# IR.net
KiCad netlist of a schematic drawn in EAGLE
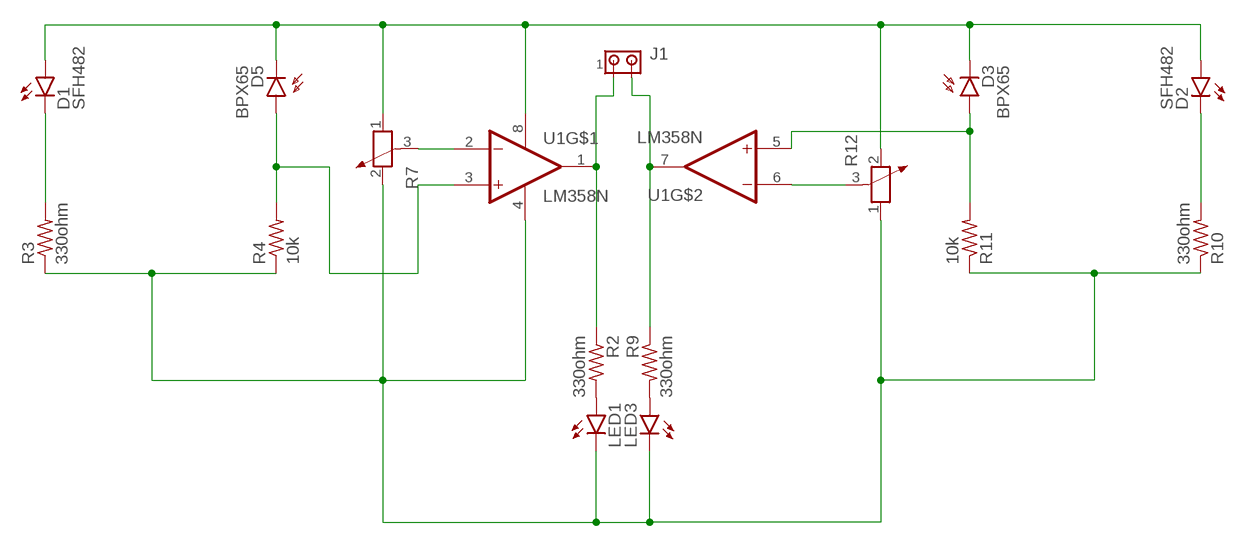
[diagram p0: schematic, sheet 1]

(export (version "E")
  (design (tool "Eeschema 10.0.6"))
  (components
    (comp (ref "D1")
      (value "SFH482")
      (footprint "eagle-import:SFH482")
      (libsource (lib "eagle-import") (part "SFH482"))
    )
    (comp (ref "D2")
      (value "SFH482")
      (footprint "eagle-import:SFH482")
      (libsource (lib "eagle-import") (part "SFH482"))
    )
    (comp (ref "D3")
      (value "BPX65")
      (footprint "eagle-import:BPX65")
      (fields (field (name "MPN") "BPX65."))
      (libsource (lib "eagle-import") (part "BPX65"))
    )
    (comp (ref "D5")
      (value "BPX65")
      (footprint "eagle-import:BPX65")
      (fields (field (name "MPN") "BPX65."))
      (libsource (lib "eagle-import") (part "BPX65"))
    )
    (comp (ref "J1")
      (value "MTA02-100")
      (footprint "eagle-import:10X02MTA")
      (libsource (lib "eagle-import") (part "MTA02-100"))
    )
    (comp (ref "LED1")
      (value "LED3MM")
      (footprint "eagle-import:LED3MM")
      (libsource (lib "eagle-import") (part "LED3MM"))
    )
    (comp (ref "LED3")
      (value "LED3MM")
      (footprint "eagle-import:LED3MM")
      (libsource (lib "eagle-import") (part "LED3MM"))
    )
    (comp (ref "R2")
      (value "330ohm")
      (footprint "eagle-import:0204_5")
      (libsource (lib "eagle-import") (part "R-US_0204/5"))
    )
    (comp (ref "R3")
      (value "330ohm")
      (footprint "eagle-import:0204_5")
      (libsource (lib "eagle-import") (part "R-US_0204/5"))
    )
    (comp (ref "R4")
      (value "10k")
      (footprint "eagle-import:0204_5")
      (libsource (lib "eagle-import") (part "R-US_0204/5"))
    )
    (comp (ref "R7")
      (value "POTENTIOMETER_PT-10")
      (footprint "eagle-import:PT-10")
      (libsource (lib "eagle-import") (part "POTENTIOMETER_PT-10"))
    )
    (comp (ref "R9")
      (value "330ohm")
      (footprint "eagle-import:0204_5")
      (libsource (lib "eagle-import") (part "R-US_0204/5"))
    )
    (comp (ref "R10")
      (value "330ohm")
      (footprint "eagle-import:0204_5")
      (libsource (lib "eagle-import") (part "R-US_0204/5"))
    )
    (comp (ref "R11")
      (value "10k")
      (footprint "eagle-import:0204_5")
      (libsource (lib "eagle-import") (part "R-US_0204/5"))
    )
    (comp (ref "R12")
      (value "POTENTIOMETER_PT-10")
      (footprint "eagle-import:PT-10")
      (libsource (lib "eagle-import") (part "POTENTIOMETER_PT-10"))
    )
    (comp (ref "U1")
      (value "LM358N")
      (footprint "eagle-import:DIP762W46P254L960H508Q8")
      (fields (field (name "MF") "Harris Corporation"))
      (libsource (lib "eagle-import") (part "LM358N"))
    )
  )
  (nets
    (net (code "1") (name "Net-(D1-C)") (class "Default")
      (node (ref "D1") (pin "K") (pinfunction "C_K") (pintype "passive"))
      (node (ref "R3") (pin "2") (pinfunction "2_2") (pintype "passive"))
    )
    (net (code "2") (name "Net-(D2-C)") (class "Default")
      (node (ref "D2") (pin "K") (pinfunction "C_K") (pintype "passive"))
      (node (ref "R10") (pin "2") (pinfunction "2_2") (pintype "passive"))
    )
    (net (code "3") (name "Net-(D3-C)") (class "Default")
      (node (ref "D1") (pin "A") (pinfunction "A_A") (pintype "passive"))
      (node (ref "D2") (pin "A") (pinfunction "A_A") (pintype "passive"))
      (node (ref "D3") (pin "K") (pinfunction "C_K") (pintype "passive"))
      (node (ref "D5") (pin "K") (pinfunction "C_K") (pintype "passive"))
      (node (ref "R12") (pin "2") (pinfunction "2_2") (pintype "passive"))
      (node (ref "R7") (pin "1") (pinfunction "1_1") (pintype "passive"))
      (node (ref "U1") (pin "8") (pinfunction "VCC_8") (pintype "power_in"))
    )
    (net (code "4") (name "Net-(LED1-C)") (class "Default")
      (node (ref "LED1") (pin "K") (pinfunction "C_K") (pintype "passive"))
      (node (ref "LED3") (pin "K") (pinfunction "C_K") (pintype "passive"))
      (node (ref "R10") (pin "1") (pinfunction "1_1") (pintype "passive"))
      (node (ref "R11") (pin "1") (pinfunction "1_1") (pintype "passive"))
      (node (ref "R12") (pin "1") (pinfunction "1_1") (pintype "passive"))
      (node (ref "R3") (pin "1") (pinfunction "1_1") (pintype "passive"))
      (node (ref "R4") (pin "1") (pinfunction "1_1") (pintype "passive"))
      (node (ref "R7") (pin "2") (pinfunction "2_2") (pintype "passive"))
      (node (ref "U1") (pin "4") (pinfunction "GND_4") (pintype "power_in"))
    )
    (net (code "5") (name "Net-(LED1-PadA)") (class "Default")
      (node (ref "LED1") (pin "A") (pinfunction "A_A") (pintype "passive"))
      (node (ref "R2") (pin "2") (pinfunction "2_2") (pintype "passive"))
    )
    (net (code "6") (name "Net-(LED3-PadA)") (class "Default")
      (node (ref "LED3") (pin "A") (pinfunction "A_A") (pintype "passive"))
      (node (ref "R9") (pin "2") (pinfunction "2_2") (pintype "passive"))
    )
    (net (code "7") (name "Net-(U1A-1IN+)") (class "Default")
      (node (ref "D5") (pin "A") (pinfunction "A_A") (pintype "passive"))
      (node (ref "R4") (pin "2") (pinfunction "2_2") (pintype "passive"))
      (node (ref "U1") (pin "3") (pinfunction "1IN+_3") (pintype "input"))
    )
    (net (code "8") (name "Net-(U1A-1IN-)") (class "Default")
      (node (ref "R7") (pin "3") (pinfunction "3_3") (pintype "passive"))
      (node (ref "U1") (pin "2") (pinfunction "1IN-_2") (pintype "input"))
    )
    (net (code "9") (name "Net-(U1A-1OUT)") (class "Default")
      (node (ref "J1") (pin "1") (pinfunction "1_1") (pintype "passive"))
      (node (ref "R2") (pin "1") (pinfunction "1_1") (pintype "passive"))
      (node (ref "U1") (pin "1") (pinfunction "1OUT_1") (pintype "output"))
    )
    (net (code "10") (name "Net-(U1B-2IN+)") (class "Default")
      (node (ref "D3") (pin "A") (pinfunction "A_A") (pintype "passive"))
      (node (ref "R11") (pin "2") (pinfunction "2_2") (pintype "passive"))
      (node (ref "U1") (pin "5") (pinfunction "2IN+_5") (pintype "input"))
    )
    (net (code "11") (name "Net-(U1B-2IN-)") (class "Default")
      (node (ref "R12") (pin "3") (pinfunction "3_3") (pintype "passive"))
      (node (ref "U1") (pin "6") (pinfunction "2IN-_6") (pintype "input"))
    )
    (net (code "12") (name "Net-(U1B-2OUT)") (class "Default")
      (node (ref "J1") (pin "2") (pinfunction "2_2") (pintype "passive"))
      (node (ref "R9") (pin "1") (pinfunction "1_1") (pintype "passive"))
      (node (ref "U1") (pin "7") (pinfunction "2OUT_7") (pintype "output"))
    )
  )
)
